# Sheet1.net
KiCad netlist of a schematic drawn in Altium Designer
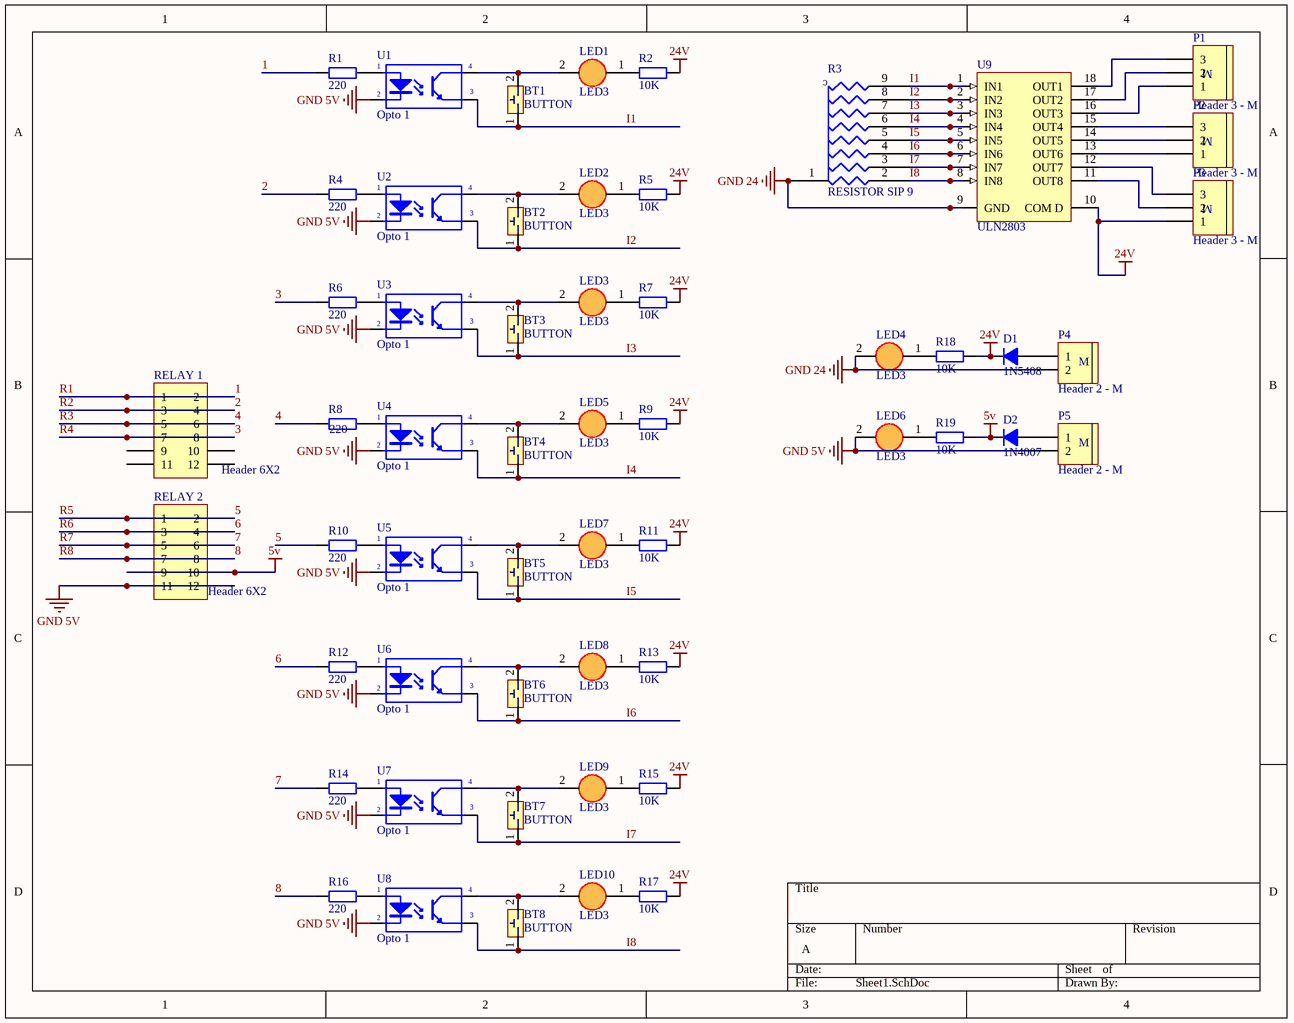
[diagram p0: Sheet1.SchDoc]

(export (version "E")
  (design (tool "Eeschema 10.0.6"))
  (components
    (comp (ref "BT1")
      (value "BUTTON")
      (footprint "button 4 pin")
      (libsource (lib "Cty1") (part "BUTTON 4 PIN"))
    )
    (comp (ref "BT2")
      (value "BUTTON")
      (footprint "button 4 pin")
      (libsource (lib "Cty1") (part "BUTTON 4 PIN"))
    )
    (comp (ref "BT3")
      (value "BUTTON")
      (footprint "button 4 pin")
      (libsource (lib "Cty1") (part "BUTTON 4 PIN"))
    )
    (comp (ref "BT4")
      (value "BUTTON")
      (footprint "button 4 pin")
      (libsource (lib "Cty1") (part "BUTTON 4 PIN"))
    )
    (comp (ref "BT5")
      (value "BUTTON")
      (footprint "button 4 pin")
      (libsource (lib "Cty1") (part "BUTTON 4 PIN"))
    )
    (comp (ref "BT6")
      (value "BUTTON")
      (footprint "button 4 pin")
      (libsource (lib "Cty1") (part "BUTTON 4 PIN"))
    )
    (comp (ref "BT7")
      (value "BUTTON")
      (footprint "button 4 pin")
      (libsource (lib "Cty1") (part "BUTTON 4 PIN"))
    )
    (comp (ref "BT8")
      (value "BUTTON")
      (footprint "button 4 pin")
      (libsource (lib "Cty1") (part "BUTTON 4 PIN"))
    )
    (comp (ref "D1")
      (value "1N5408")
      (footprint "D5A")
      (description "Diode 5A")
      (libsource (lib "Cty1") (part "D5A"))
    )
    (comp (ref "D2")
      (value "1N4007")
      (footprint "D1A")
      (description "Diode 1A")
      (libsource (lib "Cty1") (part "D1A"))
    )
    (comp (ref "LED1")
      (value "LED3")
      (footprint "LED3mm")
      (description "LED 3mm")
      (libsource (lib "Cty1") (part "LED 3mm"))
    )
    (comp (ref "LED2")
      (value "LED3")
      (footprint "LED3mm")
      (description "LED 3mm")
      (libsource (lib "Cty1") (part "LED 3mm"))
    )
    (comp (ref "LED3")
      (value "LED3")
      (footprint "LED3mm")
      (description "LED 3mm")
      (libsource (lib "Cty1") (part "LED 3mm"))
    )
    (comp (ref "LED4")
      (value "LED3")
      (footprint "LED3mm")
      (description "LED 3mm")
      (libsource (lib "Cty1") (part "LED 3mm"))
    )
    (comp (ref "LED5")
      (value "LED3")
      (footprint "LED3mm")
      (description "LED 3mm")
      (libsource (lib "Cty1") (part "LED 3mm"))
    )
    (comp (ref "LED6")
      (value "LED3")
      (footprint "LED3mm")
      (description "LED 3mm")
      (libsource (lib "Cty1") (part "LED 3mm"))
    )
    (comp (ref "LED7")
      (value "LED3")
      (footprint "LED3mm")
      (description "LED 3mm")
      (libsource (lib "Cty1") (part "LED 3mm"))
    )
    (comp (ref "LED8")
      (value "LED3")
      (footprint "LED3mm")
      (description "LED 3mm")
      (libsource (lib "Cty1") (part "LED 3mm"))
    )
    (comp (ref "LED9")
      (value "LED3")
      (footprint "LED3mm")
      (description "LED 3mm")
      (libsource (lib "Cty1") (part "LED 3mm"))
    )
    (comp (ref "LED10")
      (value "LED3")
      (footprint "LED3mm")
      (description "LED 3mm")
      (libsource (lib "Cty1") (part "LED 3mm"))
    )
    (comp (ref "P1")
      (value "Header 3 - M")
      (footprint "Medium - Header 3")
      (description "Header, 3-Pin, Medium")
      (fields (field (name "PUBLISHER") "Altium Limited"))
      (libsource (lib "Cty1") (part "Header 3 - M"))
    )
    (comp (ref "P2")
      (value "Header 3 - M")
      (footprint "Medium - Header 3")
      (description "Header, 3-Pin, Medium")
      (fields (field (name "PUBLISHER") "Altium Limited"))
      (libsource (lib "Cty1") (part "Header 3 - M"))
    )
    (comp (ref "P3")
      (value "Header 3 - M")
      (footprint "Medium - Header 3")
      (description "Header, 3-Pin, Medium")
      (fields (field (name "PUBLISHER") "Altium Limited"))
      (libsource (lib "Cty1") (part "Header 3 - M"))
    )
    (comp (ref "P4")
      (value "Header 2 - M")
      (footprint "Medium - Header 2")
      (description "Header, 2-Pin, Medium")
      (fields (field (name "PUBLISHER") "Altium Limited"))
      (libsource (lib "Cty1") (part "Header 2 - M"))
    )
    (comp (ref "P5")
      (value "Header 2 - M")
      (footprint "Medium - Header 2")
      (description "Header, 2-Pin, Medium")
      (fields (field (name "PUBLISHER") "Altium Limited"))
      (libsource (lib "Cty1") (part "Header 2 - M"))
    )
    (comp (ref "R1")
      (value "220")
      (footprint "R1/4W")
      (description "Resistor 1/4W")
      (libsource (lib "Cty1") (part "R1/4W"))
    )
    (comp (ref "R2")
      (value "10K")
      (footprint "R1/4W")
      (description "Resistor 1/4W")
      (libsource (lib "Cty1") (part "R1/4W"))
    )
    (comp (ref "R3")
      (value "RESISTOR SIP 9")
      (footprint "HDR1X9")
      (libsource (lib "Cty1") (part "RESISTOR SIP 9"))
    )
    (comp (ref "R4")
      (value "220")
      (footprint "R1/4W")
      (description "Resistor 1/4W")
      (libsource (lib "Cty1") (part "R1/4W"))
    )
    (comp (ref "R5")
      (value "10K")
      (footprint "R1/4W")
      (description "Resistor 1/4W")
      (libsource (lib "Cty1") (part "R1/4W"))
    )
    (comp (ref "R6")
      (value "220")
      (footprint "R1/4W")
      (description "Resistor 1/4W")
      (libsource (lib "Cty1") (part "R1/4W"))
    )
    (comp (ref "R7")
      (value "10K")
      (footprint "R1/4W")
      (description "Resistor 1/4W")
      (libsource (lib "Cty1") (part "R1/4W"))
    )
    (comp (ref "R8")
      (value "220")
      (footprint "R1/4W")
      (description "Resistor 1/4W")
      (libsource (lib "Cty1") (part "R1/4W"))
    )
    (comp (ref "R9")
      (value "10K")
      (footprint "R1/4W")
      (description "Resistor 1/4W")
      (libsource (lib "Cty1") (part "R1/4W"))
    )
    (comp (ref "R10")
      (value "220")
      (footprint "R1/4W")
      (description "Resistor 1/4W")
      (libsource (lib "Cty1") (part "R1/4W"))
    )
    (comp (ref "R11")
      (value "10K")
      (footprint "R1/4W")
      (description "Resistor 1/4W")
      (libsource (lib "Cty1") (part "R1/4W"))
    )
    (comp (ref "R12")
      (value "220")
      (footprint "R1/4W")
      (description "Resistor 1/4W")
      (libsource (lib "Cty1") (part "R1/4W"))
    )
    (comp (ref "R13")
      (value "10K")
      (footprint "R1/4W")
      (description "Resistor 1/4W")
      (libsource (lib "Cty1") (part "R1/4W"))
    )
    (comp (ref "R14")
      (value "220")
      (footprint "R1/4W")
      (description "Resistor 1/4W")
      (libsource (lib "Cty1") (part "R1/4W"))
    )
    (comp (ref "R15")
      (value "10K")
      (footprint "R1/4W")
      (description "Resistor 1/4W")
      (libsource (lib "Cty1") (part "R1/4W"))
    )
    (comp (ref "R16")
      (value "220")
      (footprint "R1/4W")
      (description "Resistor 1/4W")
      (libsource (lib "Cty1") (part "R1/4W"))
    )
    (comp (ref "R17")
      (value "10K")
      (footprint "R1/4W")
      (description "Resistor 1/4W")
      (libsource (lib "Cty1") (part "R1/4W"))
    )
    (comp (ref "R18")
      (value "10K")
      (footprint "R1/4W")
      (description "Resistor 1/4W")
      (libsource (lib "Cty1") (part "R1/4W"))
    )
    (comp (ref "R19")
      (value "10K")
      (footprint "R1/4W")
      (description "Resistor 1/4W")
      (libsource (lib "Cty1") (part "R1/4W"))
    )
    (comp (ref "RELAY 1")
      (value "Header 6X2")
      (footprint "HDR2X6")
      (description "Header, 6-Pin, Dual row")
      (fields (field (name "PUBLISHER") "Altium Limited"))
      (libsource (lib "Cty1") (part "Header 6X2"))
    )
    (comp (ref "RELAY 2")
      (value "Header 6X2")
      (footprint "HDR2X6")
      (description "Header, 6-Pin, Dual row")
      (fields (field (name "PUBLISHER") "Altium Limited"))
      (libsource (lib "Cty1") (part "Header 6X2"))
    )
    (comp (ref "U1")
      (value "Opto 1")
      (footprint "DIP4")
      (description "Single")
      (libsource (lib "Cty1") (part "Opto 1"))
    )
    (comp (ref "U2")
      (value "Opto 1")
      (footprint "DIP4")
      (description "Single")
      (libsource (lib "Cty1") (part "Opto 1"))
    )
    (comp (ref "U3")
      (value "Opto 1")
      (footprint "DIP4")
      (description "Single")
      (libsource (lib "Cty1") (part "Opto 1"))
    )
    (comp (ref "U4")
      (value "Opto 1")
      (footprint "DIP4")
      (description "Single")
      (libsource (lib "Cty1") (part "Opto 1"))
    )
    (comp (ref "U5")
      (value "Opto 1")
      (footprint "DIP4")
      (description "Single")
      (libsource (lib "Cty1") (part "Opto 1"))
    )
    (comp (ref "U6")
      (value "Opto 1")
      (footprint "DIP4")
      (description "Single")
      (libsource (lib "Cty1") (part "Opto 1"))
    )
    (comp (ref "U7")
      (value "Opto 1")
      (footprint "DIP4")
      (description "Single")
      (libsource (lib "Cty1") (part "Opto 1"))
    )
    (comp (ref "U8")
      (value "Opto 1")
      (footprint "DIP4")
      (description "Single")
      (libsource (lib "Cty1") (part "Opto 1"))
    )
    (comp (ref "U9")
      (value "ULN2803")
      (footprint "ThuvienPCB:DIP 18")
      (fields (field (name "Comment") "IC"))
      (libsource (lib "THU VIEN NGUYEN LY") (part "ULN2803"))
    )
  )
  (nets
    (net (code "1") (name "/1") (class "Default")
      (node (ref "R1") (pin "1") (pinfunction "1_1") (pintype "passive"))
      (node (ref "RELAY 1") (pin "1") (pinfunction "1_1") (pintype "passive"))
      (node (ref "RELAY 1") (pin "2") (pinfunction "2_2") (pintype "passive"))
    )
    (net (code "2") (name "/2") (class "Default")
      (node (ref "R4") (pin "1") (pinfunction "1_1") (pintype "passive"))
      (node (ref "RELAY 1") (pin "3") (pinfunction "3_3") (pintype "passive"))
      (node (ref "RELAY 1") (pin "4") (pinfunction "4_4") (pintype "passive"))
    )
    (net (code "3") (name "/3") (class "Default")
      (node (ref "R6") (pin "1") (pinfunction "1_1") (pintype "passive"))
      (node (ref "RELAY 1") (pin "7") (pinfunction "7_7") (pintype "passive"))
      (node (ref "RELAY 1") (pin "8") (pinfunction "8_8") (pintype "passive"))
    )
    (net (code "4") (name "/4") (class "Default")
      (node (ref "R8") (pin "1") (pinfunction "1_1") (pintype "passive"))
      (node (ref "RELAY 1") (pin "5") (pinfunction "5_5") (pintype "passive"))
      (node (ref "RELAY 1") (pin "6") (pinfunction "6_6") (pintype "passive"))
    )
    (net (code "5") (name "/5") (class "Default")
      (node (ref "R10") (pin "1") (pinfunction "1_1") (pintype "passive"))
      (node (ref "RELAY 2") (pin "1") (pinfunction "1_1") (pintype "passive"))
      (node (ref "RELAY 2") (pin "2") (pinfunction "2_2") (pintype "passive"))
    )
    (net (code "6") (name "/6") (class "Default")
      (node (ref "R12") (pin "1") (pinfunction "1_1") (pintype "passive"))
      (node (ref "RELAY 2") (pin "3") (pinfunction "3_3") (pintype "passive"))
      (node (ref "RELAY 2") (pin "4") (pinfunction "4_4") (pintype "passive"))
    )
    (net (code "7") (name "/7") (class "Default")
      (node (ref "R14") (pin "1") (pinfunction "1_1") (pintype "passive"))
      (node (ref "RELAY 2") (pin "5") (pinfunction "5_5") (pintype "passive"))
      (node (ref "RELAY 2") (pin "6") (pinfunction "6_6") (pintype "passive"))
    )
    (net (code "8") (name "/8") (class "Default")
      (node (ref "R16") (pin "1") (pinfunction "1_1") (pintype "passive"))
      (node (ref "RELAY 2") (pin "7") (pinfunction "7_7") (pintype "passive"))
      (node (ref "RELAY 2") (pin "8") (pinfunction "8_8") (pintype "passive"))
    )
    (net (code "9") (name "/I1") (class "Default")
      (node (ref "BT1") (pin "1") (pinfunction "1_1") (pintype "passive"))
      (node (ref "R3") (pin "9") (pinfunction "9_9") (pintype "passive"))
      (node (ref "U1") (pin "3") (pinfunction "E_3") (pintype "passive"))
      (node (ref "U9") (pin "1") (pinfunction "IN1_1") (pintype "input"))
    )
    (net (code "10") (name "/I2") (class "Default")
      (node (ref "BT2") (pin "1") (pinfunction "1_1") (pintype "passive"))
      (node (ref "R3") (pin "8") (pinfunction "8_8") (pintype "passive"))
      (node (ref "U2") (pin "3") (pinfunction "E_3") (pintype "passive"))
      (node (ref "U9") (pin "2") (pinfunction "IN2_2") (pintype "input"))
    )
    (net (code "11") (name "/I3") (class "Default")
      (node (ref "BT3") (pin "1") (pinfunction "1_1") (pintype "passive"))
      (node (ref "R3") (pin "7") (pinfunction "7_7") (pintype "passive"))
      (node (ref "U3") (pin "3") (pinfunction "E_3") (pintype "passive"))
      (node (ref "U9") (pin "3") (pinfunction "IN3_3") (pintype "input"))
    )
    (net (code "12") (name "/I4") (class "Default")
      (node (ref "BT4") (pin "1") (pinfunction "1_1") (pintype "passive"))
      (node (ref "R3") (pin "6") (pinfunction "6_6") (pintype "passive"))
      (node (ref "U4") (pin "3") (pinfunction "E_3") (pintype "passive"))
      (node (ref "U9") (pin "4") (pinfunction "IN4_4") (pintype "input"))
    )
    (net (code "13") (name "/I5") (class "Default")
      (node (ref "BT5") (pin "1") (pinfunction "1_1") (pintype "passive"))
      (node (ref "R3") (pin "5") (pinfunction "5_5") (pintype "passive"))
      (node (ref "U5") (pin "3") (pinfunction "E_3") (pintype "passive"))
      (node (ref "U9") (pin "5") (pinfunction "IN5_5") (pintype "input"))
    )
    (net (code "14") (name "/I6") (class "Default")
      (node (ref "BT6") (pin "1") (pinfunction "1_1") (pintype "passive"))
      (node (ref "R3") (pin "4") (pinfunction "4_4") (pintype "passive"))
      (node (ref "U6") (pin "3") (pinfunction "E_3") (pintype "passive"))
      (node (ref "U9") (pin "6") (pinfunction "IN6_6") (pintype "input"))
    )
    (net (code "15") (name "/I7") (class "Default")
      (node (ref "BT7") (pin "1") (pinfunction "1_1") (pintype "passive"))
      (node (ref "R3") (pin "3") (pinfunction "3_3") (pintype "passive"))
      (node (ref "U7") (pin "3") (pinfunction "E_3") (pintype "passive"))
      (node (ref "U9") (pin "7") (pinfunction "IN7_7") (pintype "input"))
    )
    (net (code "16") (name "/I8") (class "Default")
      (node (ref "BT8") (pin "1") (pinfunction "1_1") (pintype "passive"))
      (node (ref "R3") (pin "2") (pinfunction "2_2") (pintype "passive"))
      (node (ref "U8") (pin "3") (pinfunction "E_3") (pintype "passive"))
      (node (ref "U9") (pin "8") (pinfunction "IN8_8") (pintype "input"))
    )
    (net (code "17") (name "5v") (class "Default")
      (node (ref "D2") (pin "2") (pinfunction "K_2") (pintype "passive"))
      (node (ref "R19") (pin "2") (pinfunction "2_2") (pintype "passive"))
      (node (ref "RELAY 2") (pin "10") (pinfunction "10_10") (pintype "passive"))
      (node (ref "RELAY 2") (pin "9") (pinfunction "9_9") (pintype "passive"))
    )
    (net (code "18") (name "24V") (class "Default")
      (node (ref "D1") (pin "2") (pinfunction "K_2") (pintype "passive"))
      (node (ref "P3") (pin "1") (pinfunction "1_1") (pintype "passive"))
      (node (ref "R11") (pin "2") (pinfunction "2_2") (pintype "passive"))
      (node (ref "R13") (pin "2") (pinfunction "2_2") (pintype "passive"))
      (node (ref "R15") (pin "2") (pinfunction "2_2") (pintype "passive"))
      (node (ref "R17") (pin "2") (pinfunction "2_2") (pintype "passive"))
      (node (ref "R18") (pin "2") (pinfunction "2_2") (pintype "passive"))
      (node (ref "R2") (pin "2") (pinfunction "2_2") (pintype "passive"))
      (node (ref "R5") (pin "2") (pinfunction "2_2") (pintype "passive"))
      (node (ref "R7") (pin "2") (pinfunction "2_2") (pintype "passive"))
      (node (ref "R9") (pin "2") (pinfunction "2_2") (pintype "passive"))
      (node (ref "U9") (pin "10") (pinfunction "COM_D_10") (pintype "passive"))
    )
    (net (code "19") (name "GND 5V") (class "Default")
      (node (ref "LED6") (pin "2") (pinfunction "K_2") (pintype "passive"))
      (node (ref "P5") (pin "2") (pinfunction "2_2") (pintype "passive"))
      (node (ref "RELAY 2") (pin "11") (pinfunction "11_11") (pintype "passive"))
      (node (ref "RELAY 2") (pin "12") (pinfunction "12_12") (pintype "passive"))
      (node (ref "U1") (pin "2") (pinfunction "K_2") (pintype "passive"))
      (node (ref "U2") (pin "2") (pinfunction "K_2") (pintype "passive"))
      (node (ref "U3") (pin "2") (pinfunction "K_2") (pintype "passive"))
      (node (ref "U4") (pin "2") (pinfunction "K_2") (pintype "passive"))
      (node (ref "U5") (pin "2") (pinfunction "K_2") (pintype "passive"))
      (node (ref "U6") (pin "2") (pinfunction "K_2") (pintype "passive"))
      (node (ref "U7") (pin "2") (pinfunction "K_2") (pintype "passive"))
      (node (ref "U8") (pin "2") (pinfunction "K_2") (pintype "passive"))
    )
    (net (code "20") (name "GND 24") (class "Default")
      (node (ref "LED4") (pin "2") (pinfunction "K_2") (pintype "passive"))
      (node (ref "P4") (pin "2") (pinfunction "2_2") (pintype "passive"))
      (node (ref "R3") (pin "1") (pinfunction "1_1") (pintype "passive"))
      (node (ref "U9") (pin "9") (pinfunction "GND_9") (pintype "power_in"))
    )
    (net (code "21") (name "Net-(D1-A)") (class "Default")
      (node (ref "D1") (pin "1") (pinfunction "A_1") (pintype "passive"))
      (node (ref "P4") (pin "1") (pinfunction "1_1") (pintype "passive"))
    )
    (net (code "22") (name "Net-(D2-A)") (class "Default")
      (node (ref "D2") (pin "1") (pinfunction "A_1") (pintype "passive"))
      (node (ref "P5") (pin "1") (pinfunction "1_1") (pintype "passive"))
    )
    (net (code "23") (name "Net-(LED1-A)") (class "Default")
      (node (ref "LED1") (pin "1") (pinfunction "A_1") (pintype "passive"))
      (node (ref "R2") (pin "1") (pinfunction "1_1") (pintype "passive"))
    )
    (net (code "24") (name "Net-(LED1-K)") (class "Default")
      (node (ref "BT1") (pin "2") (pinfunction "2_2") (pintype "passive"))
      (node (ref "LED1") (pin "2") (pinfunction "K_2") (pintype "passive"))
      (node (ref "U1") (pin "4") (pinfunction "C_4") (pintype "passive"))
    )
    (net (code "25") (name "Net-(LED2-A)") (class "Default")
      (node (ref "LED2") (pin "1") (pinfunction "A_1") (pintype "passive"))
      (node (ref "R5") (pin "1") (pinfunction "1_1") (pintype "passive"))
    )
    (net (code "26") (name "Net-(LED2-K)") (class "Default")
      (node (ref "BT2") (pin "2") (pinfunction "2_2") (pintype "passive"))
      (node (ref "LED2") (pin "2") (pinfunction "K_2") (pintype "passive"))
      (node (ref "U2") (pin "4") (pinfunction "C_4") (pintype "passive"))
    )
    (net (code "27") (name "Net-(LED3-A)") (class "Default")
      (node (ref "LED3") (pin "1") (pinfunction "A_1") (pintype "passive"))
      (node (ref "R7") (pin "1") (pinfunction "1_1") (pintype "passive"))
    )
    (net (code "28") (name "Net-(LED3-K)") (class "Default")
      (node (ref "BT3") (pin "2") (pinfunction "2_2") (pintype "passive"))
      (node (ref "LED3") (pin "2") (pinfunction "K_2") (pintype "passive"))
      (node (ref "U3") (pin "4") (pinfunction "C_4") (pintype "passive"))
    )
    (net (code "29") (name "Net-(LED4-A)") (class "Default")
      (node (ref "LED4") (pin "1") (pinfunction "A_1") (pintype "passive"))
      (node (ref "R18") (pin "1") (pinfunction "1_1") (pintype "passive"))
    )
    (net (code "30") (name "Net-(LED5-A)") (class "Default")
      (node (ref "LED5") (pin "1") (pinfunction "A_1") (pintype "passive"))
      (node (ref "R9") (pin "1") (pinfunction "1_1") (pintype "passive"))
    )
    (net (code "31") (name "Net-(LED5-K)") (class "Default")
      (node (ref "BT4") (pin "2") (pinfunction "2_2") (pintype "passive"))
      (node (ref "LED5") (pin "2") (pinfunction "K_2") (pintype "passive"))
      (node (ref "U4") (pin "4") (pinfunction "C_4") (pintype "passive"))
    )
    (net (code "32") (name "Net-(LED6-A)") (class "Default")
      (node (ref "LED6") (pin "1") (pinfunction "A_1") (pintype "passive"))
      (node (ref "R19") (pin "1") (pinfunction "1_1") (pintype "passive"))
    )
    (net (code "33") (name "Net-(LED7-A)") (class "Default")
      (node (ref "LED7") (pin "1") (pinfunction "A_1") (pintype "passive"))
      (node (ref "R11") (pin "1") (pinfunction "1_1") (pintype "passive"))
    )
    (net (code "34") (name "Net-(LED7-K)") (class "Default")
      (node (ref "BT5") (pin "2") (pinfunction "2_2") (pintype "passive"))
      (node (ref "LED7") (pin "2") (pinfunction "K_2") (pintype "passive"))
      (node (ref "U5") (pin "4") (pinfunction "C_4") (pintype "passive"))
    )
    (net (code "35") (name "Net-(LED8-A)") (class "Default")
      (node (ref "LED8") (pin "1") (pinfunction "A_1") (pintype "passive"))
      (node (ref "R13") (pin "1") (pinfunction "1_1") (pintype "passive"))
    )
    (net (code "36") (name "Net-(LED8-K)") (class "Default")
      (node (ref "BT6") (pin "2") (pinfunction "2_2") (pintype "passive"))
      (node (ref "LED8") (pin "2") (pinfunction "K_2") (pintype "passive"))
      (node (ref "U6") (pin "4") (pinfunction "C_4") (pintype "passive"))
    )
    (net (code "37") (name "Net-(LED9-A)") (class "Default")
      (node (ref "LED9") (pin "1") (pinfunction "A_1") (pintype "passive"))
      (node (ref "R15") (pin "1") (pinfunction "1_1") (pintype "passive"))
    )
    (net (code "38") (name "Net-(LED9-K)") (class "Default")
      (node (ref "BT7") (pin "2") (pinfunction "2_2") (pintype "passive"))
      (node (ref "LED9") (pin "2") (pinfunction "K_2") (pintype "passive"))
      (node (ref "U7") (pin "4") (pinfunction "C_4") (pintype "passive"))
    )
    (net (code "39") (name "Net-(LED10-A)") (class "Default")
      (node (ref "LED10") (pin "1") (pinfunction "A_1") (pintype "passive"))
      (node (ref "R17") (pin "1") (pinfunction "1_1") (pintype "passive"))
    )
    (net (code "40") (name "Net-(LED10-K)") (class "Default")
      (node (ref "BT8") (pin "2") (pinfunction "2_2") (pintype "passive"))
      (node (ref "LED10") (pin "2") (pinfunction "K_2") (pintype "passive"))
      (node (ref "U8") (pin "4") (pinfunction "C_4") (pintype "passive"))
    )
    (net (code "41") (name "Net-(U1-A)") (class "Default")
      (node (ref "R1") (pin "2") (pinfunction "2_2") (pintype "passive"))
      (node (ref "U1") (pin "1") (pinfunction "A_1") (pintype "passive"))
    )
    (net (code "42") (name "Net-(U2-A)") (class "Default")
      (node (ref "R4") (pin "2") (pinfunction "2_2") (pintype "passive"))
      (node (ref "U2") (pin "1") (pinfunction "A_1") (pintype "passive"))
    )
    (net (code "43") (name "Net-(U3-A)") (class "Default")
      (node (ref "R6") (pin "2") (pinfunction "2_2") (pintype "passive"))
      (node (ref "U3") (pin "1") (pinfunction "A_1") (pintype "passive"))
    )
    (net (code "44") (name "Net-(U4-A)") (class "Default")
      (node (ref "R8") (pin "2") (pinfunction "2_2") (pintype "passive"))
      (node (ref "U4") (pin "1") (pinfunction "A_1") (pintype "passive"))
    )
    (net (code "45") (name "Net-(U5-A)") (class "Default")
      (node (ref "R10") (pin "2") (pinfunction "2_2") (pintype "passive"))
      (node (ref "U5") (pin "1") (pinfunction "A_1") (pintype "passive"))
    )
    (net (code "46") (name "Net-(U6-A)") (class "Default")
      (node (ref "R12") (pin "2") (pinfunction "2_2") (pintype "passive"))
      (node (ref "U6") (pin "1") (pinfunction "A_1") (pintype "passive"))
    )
    (net (code "47") (name "Net-(U7-A)") (class "Default")
      (node (ref "R14") (pin "2") (pinfunction "2_2") (pintype "passive"))
      (node (ref "U7") (pin "1") (pinfunction "A_1") (pintype "passive"))
    )
    (net (code "48") (name "Net-(U8-A)") (class "Default")
      (node (ref "R16") (pin "2") (pinfunction "2_2") (pintype "passive"))
      (node (ref "U8") (pin "1") (pinfunction "A_1") (pintype "passive"))
    )
    (net (code "49") (name "Net-(U9-OUT1)") (class "Default")
      (node (ref "P1") (pin "3") (pinfunction "3_3") (pintype "passive"))
      (node (ref "U9") (pin "18") (pinfunction "OUT1_18") (pintype "open_collector"))
    )
    (net (code "50") (name "Net-(U9-OUT2)") (class "Default")
      (node (ref "P1") (pin "2") (pinfunction "2_2") (pintype "passive"))
      (node (ref "U9") (pin "17") (pinfunction "OUT2_17") (pintype "open_collector"))
    )
    (net (code "51") (name "Net-(U9-OUT3)") (class "Default")
      (node (ref "P1") (pin "1") (pinfunction "1_1") (pintype "passive"))
      (node (ref "U9") (pin "16") (pinfunction "OUT3_16") (pintype "open_collector"))
    )
    (net (code "52") (name "Net-(U9-OUT4)") (class "Default")
      (node (ref "P2") (pin "3") (pinfunction "3_3") (pintype "passive"))
      (node (ref "U9") (pin "15") (pinfunction "OUT4_15") (pintype "open_collector"))
    )
    (net (code "53") (name "Net-(U9-OUT5)") (class "Default")
      (node (ref "P2") (pin "2") (pinfunction "2_2") (pintype "passive"))
      (node (ref "U9") (pin "14") (pinfunction "OUT5_14") (pintype "open_collector"))
    )
    (net (code "54") (name "Net-(U9-OUT6)") (class "Default")
      (node (ref "P2") (pin "1") (pinfunction "1_1") (pintype "passive"))
      (node (ref "U9") (pin "13") (pinfunction "OUT6_13") (pintype "open_collector"))
    )
    (net (code "55") (name "Net-(U9-OUT7)") (class "Default")
      (node (ref "P3") (pin "3") (pinfunction "3_3") (pintype "passive"))
      (node (ref "U9") (pin "12") (pinfunction "OUT7_12") (pintype "open_collector"))
    )
    (net (code "56") (name "Net-(U9-OUT8)") (class "Default")
      (node (ref "P3") (pin "2") (pinfunction "2_2") (pintype "passive"))
      (node (ref "U9") (pin "11") (pinfunction "OUT8_11") (pintype "open_collector"))
    )
    (net (code "57") (name "unconnected-(RELAY 1-Pad9)") (class "Default")
      (node (ref "RELAY 1") (pin "9") (pinfunction "9_9") (pintype "passive"))
    )
    (net (code "58") (name "unconnected-(RELAY 1-Pad10)") (class "Default")
      (node (ref "RELAY 1") (pin "10") (pinfunction "10_10") (pintype "passive"))
    )
    (net (code "59") (name "unconnected-(RELAY 1-Pad11)") (class "Default")
      (node (ref "RELAY 1") (pin "11") (pinfunction "11_11") (pintype "passive"))
    )
    (net (code "60") (name "unconnected-(RELAY 1-Pad12)") (class "Default")
      (node (ref "RELAY 1") (pin "12") (pinfunction "12_12") (pintype "passive"))
    )
  )
)
